# smd-to-breadboard2.net
KiCad netlist of a schematic drawn in EAGLE
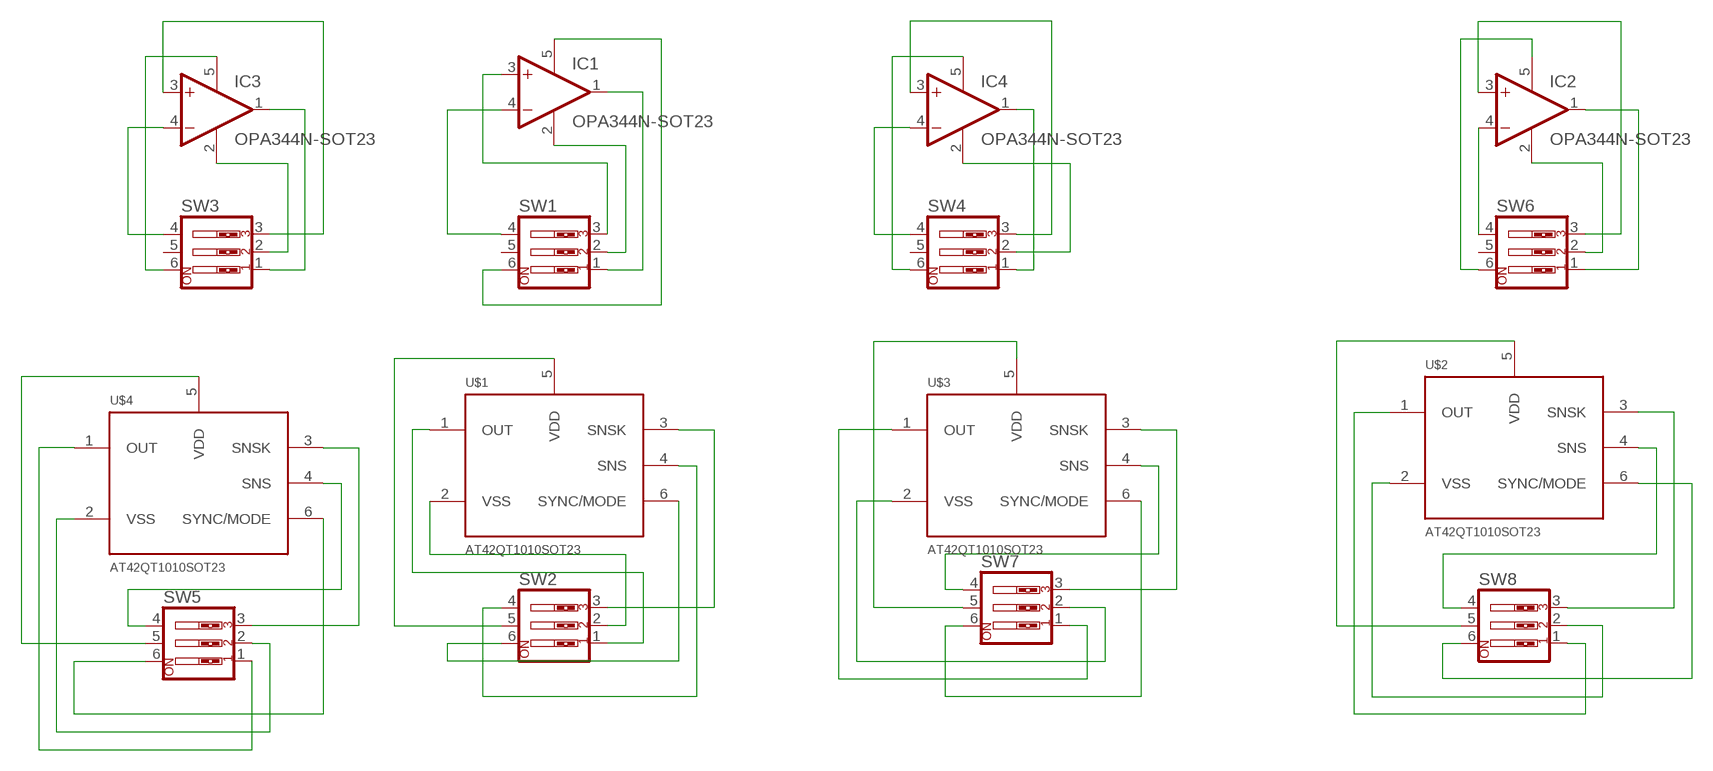
[diagram p0: schematic, sheet 1]

(export (version "E")
  (design (tool "Eeschema 10.0.6"))
  (components
    (comp (ref "IC1")
      (value "OPA344N-SOT23")
      (footprint "eagle-import:SOT23-5")
      (libsource (lib "eagle-import") (part "OPA-SOT23344N"))
    )
    (comp (ref "IC2")
      (value "OPA344N-SOT23")
      (footprint "eagle-import:SOT23-5")
      (libsource (lib "eagle-import") (part "OPA-SOT23344N"))
    )
    (comp (ref "IC3")
      (value "OPA344N-SOT23")
      (footprint "eagle-import:SOT23-5")
      (libsource (lib "eagle-import") (part "OPA-SOT23344N"))
    )
    (comp (ref "IC4")
      (value "OPA344N-SOT23")
      (footprint "eagle-import:SOT23-5")
      (libsource (lib "eagle-import") (part "OPA-SOT23344N"))
    )
    (comp (ref "SW1")
      (value "SW_DIP-3")
      (footprint "eagle-import:EDG-03")
      (libsource (lib "eagle-import") (part "SW_DIP-3"))
    )
    (comp (ref "SW2")
      (value "SW_DIP-3")
      (footprint "eagle-import:EDG-03")
      (libsource (lib "eagle-import") (part "SW_DIP-3"))
    )
    (comp (ref "SW3")
      (value "SW_DIP-3")
      (footprint "eagle-import:EDG-03")
      (libsource (lib "eagle-import") (part "SW_DIP-3"))
    )
    (comp (ref "SW4")
      (value "SW_DIP-3")
      (footprint "eagle-import:EDG-03")
      (libsource (lib "eagle-import") (part "SW_DIP-3"))
    )
    (comp (ref "SW5")
      (value "SW_DIP-3")
      (footprint "eagle-import:EDG-03")
      (libsource (lib "eagle-import") (part "SW_DIP-3"))
    )
    (comp (ref "SW6")
      (value "SW_DIP-3")
      (footprint "eagle-import:EDG-03")
      (libsource (lib "eagle-import") (part "SW_DIP-3"))
    )
    (comp (ref "SW7")
      (value "SW_DIP-3")
      (footprint "eagle-import:EDG-03")
      (libsource (lib "eagle-import") (part "SW_DIP-3"))
    )
    (comp (ref "SW8")
      (value "SW_DIP-3")
      (footprint "eagle-import:EDG-03")
      (libsource (lib "eagle-import") (part "SW_DIP-3"))
    )
    (comp (ref "U$1")
      (value "AT42QT1010SOT23")
      (footprint "eagle-import:SOT23-6")
      (libsource (lib "eagle-import") (part "AT42QT1010SOT23"))
    )
    (comp (ref "U$2")
      (value "AT42QT1010SOT23")
      (footprint "eagle-import:SOT23-6")
      (libsource (lib "eagle-import") (part "AT42QT1010SOT23"))
    )
    (comp (ref "U$3")
      (value "AT42QT1010SOT23")
      (footprint "eagle-import:SOT23-6")
      (libsource (lib "eagle-import") (part "AT42QT1010SOT23"))
    )
    (comp (ref "U$4")
      (value "AT42QT1010SOT23")
      (footprint "eagle-import:SOT23-6")
      (libsource (lib "eagle-import") (part "AT42QT1010SOT23"))
    )
  )
  (nets
    (net (code "1") (name "Net-(IC1-+IN)") (class "Default")
      (node (ref "IC1") (pin "3") (pinfunction "+IN_3") (pintype "input"))
      (node (ref "SW1") (pin "3") (pinfunction "3_3") (pintype "passive"))
    )
    (net (code "2") (name "Net-(IC1--IN)") (class "Default")
      (node (ref "IC1") (pin "4") (pinfunction "-IN_4") (pintype "input"))
      (node (ref "SW1") (pin "4") (pinfunction "4_4") (pintype "passive"))
    )
    (net (code "3") (name "Net-(IC1-OUT)") (class "Default")
      (node (ref "IC1") (pin "1") (pinfunction "OUT_1") (pintype "output"))
      (node (ref "SW1") (pin "1") (pinfunction "1_1") (pintype "passive"))
    )
    (net (code "4") (name "Net-(IC1-V+)") (class "Default")
      (node (ref "IC1") (pin "5") (pinfunction "V+_5") (pintype "power_in"))
      (node (ref "SW1") (pin "6") (pinfunction "6_6") (pintype "passive"))
    )
    (net (code "5") (name "Net-(IC1-V-)") (class "Default")
      (node (ref "IC1") (pin "2") (pinfunction "V-_2") (pintype "power_in"))
      (node (ref "SW1") (pin "2") (pinfunction "2_2") (pintype "passive"))
    )
    (net (code "6") (name "Net-(IC2-+IN)") (class "Default")
      (node (ref "IC2") (pin "3") (pinfunction "+IN_3") (pintype "input"))
      (node (ref "SW6") (pin "3") (pinfunction "3_3") (pintype "passive"))
    )
    (net (code "7") (name "Net-(IC2--IN)") (class "Default")
      (node (ref "IC2") (pin "4") (pinfunction "-IN_4") (pintype "input"))
      (node (ref "SW6") (pin "4") (pinfunction "4_4") (pintype "passive"))
    )
    (net (code "8") (name "Net-(IC2-OUT)") (class "Default")
      (node (ref "IC2") (pin "1") (pinfunction "OUT_1") (pintype "output"))
      (node (ref "SW6") (pin "1") (pinfunction "1_1") (pintype "passive"))
    )
    (net (code "9") (name "Net-(IC2-V+)") (class "Default")
      (node (ref "IC2") (pin "5") (pinfunction "V+_5") (pintype "power_in"))
      (node (ref "SW6") (pin "6") (pinfunction "6_6") (pintype "passive"))
    )
    (net (code "10") (name "Net-(IC2-V-)") (class "Default")
      (node (ref "IC2") (pin "2") (pinfunction "V-_2") (pintype "power_in"))
      (node (ref "SW6") (pin "2") (pinfunction "2_2") (pintype "passive"))
    )
    (net (code "11") (name "Net-(IC3-+IN)") (class "Default")
      (node (ref "IC3") (pin "3") (pinfunction "+IN_3") (pintype "input"))
      (node (ref "SW3") (pin "3") (pinfunction "3_3") (pintype "passive"))
    )
    (net (code "12") (name "Net-(IC3--IN)") (class "Default")
      (node (ref "IC3") (pin "4") (pinfunction "-IN_4") (pintype "input"))
      (node (ref "SW3") (pin "4") (pinfunction "4_4") (pintype "passive"))
    )
    (net (code "13") (name "Net-(IC3-OUT)") (class "Default")
      (node (ref "IC3") (pin "1") (pinfunction "OUT_1") (pintype "output"))
      (node (ref "SW3") (pin "1") (pinfunction "1_1") (pintype "passive"))
    )
    (net (code "14") (name "Net-(IC3-V+)") (class "Default")
      (node (ref "IC3") (pin "5") (pinfunction "V+_5") (pintype "power_in"))
      (node (ref "SW3") (pin "6") (pinfunction "6_6") (pintype "passive"))
    )
    (net (code "15") (name "Net-(IC3-V-)") (class "Default")
      (node (ref "IC3") (pin "2") (pinfunction "V-_2") (pintype "power_in"))
      (node (ref "SW3") (pin "2") (pinfunction "2_2") (pintype "passive"))
    )
    (net (code "16") (name "Net-(IC4-+IN)") (class "Default")
      (node (ref "IC4") (pin "3") (pinfunction "+IN_3") (pintype "input"))
      (node (ref "SW4") (pin "3") (pinfunction "3_3") (pintype "passive"))
    )
    (net (code "17") (name "Net-(IC4--IN)") (class "Default")
      (node (ref "IC4") (pin "4") (pinfunction "-IN_4") (pintype "input"))
      (node (ref "SW4") (pin "4") (pinfunction "4_4") (pintype "passive"))
    )
    (net (code "18") (name "Net-(IC4-OUT)") (class "Default")
      (node (ref "IC4") (pin "1") (pinfunction "OUT_1") (pintype "output"))
      (node (ref "SW4") (pin "1") (pinfunction "1_1") (pintype "passive"))
    )
    (net (code "19") (name "Net-(IC4-V+)") (class "Default")
      (node (ref "IC4") (pin "5") (pinfunction "V+_5") (pintype "power_in"))
      (node (ref "SW4") (pin "6") (pinfunction "6_6") (pintype "passive"))
    )
    (net (code "20") (name "Net-(IC4-V-)") (class "Default")
      (node (ref "IC4") (pin "2") (pinfunction "V-_2") (pintype "power_in"))
      (node (ref "SW4") (pin "2") (pinfunction "2_2") (pintype "passive"))
    )
    (net (code "21") (name "Net-(U$1-OUT)") (class "Default")
      (node (ref "SW2") (pin "1") (pinfunction "1_1") (pintype "passive"))
      (node (ref "U$1") (pin "1") (pinfunction "OUT_1") (pintype "bidirectional"))
    )
    (net (code "22") (name "Net-(U$1-SNS)") (class "Default")
      (node (ref "SW2") (pin "4") (pinfunction "4_4") (pintype "passive"))
      (node (ref "U$1") (pin "4") (pinfunction "SNS_4") (pintype "bidirectional"))
    )
    (net (code "23") (name "Net-(U$1-SNSK)") (class "Default")
      (node (ref "SW2") (pin "3") (pinfunction "3_3") (pintype "passive"))
      (node (ref "U$1") (pin "3") (pinfunction "SNSK_3") (pintype "bidirectional"))
    )
    (net (code "24") (name "Net-(U$1-SYNC{slash}MODE)") (class "Default")
      (node (ref "SW2") (pin "6") (pinfunction "6_6") (pintype "passive"))
      (node (ref "U$1") (pin "6") (pinfunction "SYNC/MODE_6") (pintype "bidirectional"))
    )
    (net (code "25") (name "Net-(U$1-VDD)") (class "Default")
      (node (ref "SW2") (pin "5") (pinfunction "5_5") (pintype "passive"))
      (node (ref "U$1") (pin "5") (pinfunction "VDD_5") (pintype "bidirectional"))
    )
    (net (code "26") (name "Net-(U$1-VSS)") (class "Default")
      (node (ref "SW2") (pin "2") (pinfunction "2_2") (pintype "passive"))
      (node (ref "U$1") (pin "2") (pinfunction "VSS_2") (pintype "bidirectional"))
    )
    (net (code "27") (name "Net-(U$2-OUT)") (class "Default")
      (node (ref "SW8") (pin "1") (pinfunction "1_1") (pintype "passive"))
      (node (ref "U$2") (pin "1") (pinfunction "OUT_1") (pintype "bidirectional"))
    )
    (net (code "28") (name "Net-(U$2-SNS)") (class "Default")
      (node (ref "SW8") (pin "4") (pinfunction "4_4") (pintype "passive"))
      (node (ref "U$2") (pin "4") (pinfunction "SNS_4") (pintype "bidirectional"))
    )
    (net (code "29") (name "Net-(U$2-SNSK)") (class "Default")
      (node (ref "SW8") (pin "3") (pinfunction "3_3") (pintype "passive"))
      (node (ref "U$2") (pin "3") (pinfunction "SNSK_3") (pintype "bidirectional"))
    )
    (net (code "30") (name "Net-(U$2-SYNC{slash}MODE)") (class "Default")
      (node (ref "SW8") (pin "6") (pinfunction "6_6") (pintype "passive"))
      (node (ref "U$2") (pin "6") (pinfunction "SYNC/MODE_6") (pintype "bidirectional"))
    )
    (net (code "31") (name "Net-(U$2-VDD)") (class "Default")
      (node (ref "SW8") (pin "5") (pinfunction "5_5") (pintype "passive"))
      (node (ref "U$2") (pin "5") (pinfunction "VDD_5") (pintype "bidirectional"))
    )
    (net (code "32") (name "Net-(U$2-VSS)") (class "Default")
      (node (ref "SW8") (pin "2") (pinfunction "2_2") (pintype "passive"))
      (node (ref "U$2") (pin "2") (pinfunction "VSS_2") (pintype "bidirectional"))
    )
    (net (code "33") (name "Net-(U$3-OUT)") (class "Default")
      (node (ref "SW7") (pin "1") (pinfunction "1_1") (pintype "passive"))
      (node (ref "U$3") (pin "1") (pinfunction "OUT_1") (pintype "bidirectional"))
    )
    (net (code "34") (name "Net-(U$3-SNS)") (class "Default")
      (node (ref "SW7") (pin "4") (pinfunction "4_4") (pintype "passive"))
      (node (ref "U$3") (pin "4") (pinfunction "SNS_4") (pintype "bidirectional"))
    )
    (net (code "35") (name "Net-(U$3-SNSK)") (class "Default")
      (node (ref "SW7") (pin "3") (pinfunction "3_3") (pintype "passive"))
      (node (ref "U$3") (pin "3") (pinfunction "SNSK_3") (pintype "bidirectional"))
    )
    (net (code "36") (name "Net-(U$3-SYNC{slash}MODE)") (class "Default")
      (node (ref "SW7") (pin "6") (pinfunction "6_6") (pintype "passive"))
      (node (ref "U$3") (pin "6") (pinfunction "SYNC/MODE_6") (pintype "bidirectional"))
    )
    (net (code "37") (name "Net-(U$3-VDD)") (class "Default")
      (node (ref "SW7") (pin "5") (pinfunction "5_5") (pintype "passive"))
      (node (ref "U$3") (pin "5") (pinfunction "VDD_5") (pintype "bidirectional"))
    )
    (net (code "38") (name "Net-(U$3-VSS)") (class "Default")
      (node (ref "SW7") (pin "2") (pinfunction "2_2") (pintype "passive"))
      (node (ref "U$3") (pin "2") (pinfunction "VSS_2") (pintype "bidirectional"))
    )
    (net (code "39") (name "Net-(U$4-OUT)") (class "Default")
      (node (ref "SW5") (pin "1") (pinfunction "1_1") (pintype "passive"))
      (node (ref "U$4") (pin "1") (pinfunction "OUT_1") (pintype "bidirectional"))
    )
    (net (code "40") (name "Net-(U$4-SNS)") (class "Default")
      (node (ref "SW5") (pin "4") (pinfunction "4_4") (pintype "passive"))
      (node (ref "U$4") (pin "4") (pinfunction "SNS_4") (pintype "bidirectional"))
    )
    (net (code "41") (name "Net-(U$4-SNSK)") (class "Default")
      (node (ref "SW5") (pin "3") (pinfunction "3_3") (pintype "passive"))
      (node (ref "U$4") (pin "3") (pinfunction "SNSK_3") (pintype "bidirectional"))
    )
    (net (code "42") (name "Net-(U$4-SYNC{slash}MODE)") (class "Default")
      (node (ref "SW5") (pin "6") (pinfunction "6_6") (pintype "passive"))
      (node (ref "U$4") (pin "6") (pinfunction "SYNC/MODE_6") (pintype "bidirectional"))
    )
    (net (code "43") (name "Net-(U$4-VDD)") (class "Default")
      (node (ref "SW5") (pin "5") (pinfunction "5_5") (pintype "passive"))
      (node (ref "U$4") (pin "5") (pinfunction "VDD_5") (pintype "bidirectional"))
    )
    (net (code "44") (name "Net-(U$4-VSS)") (class "Default")
      (node (ref "SW5") (pin "2") (pinfunction "2_2") (pintype "passive"))
      (node (ref "U$4") (pin "2") (pinfunction "VSS_2") (pintype "bidirectional"))
    )
    (net (code "45") (name "unconnected-(SW1-Pad5)") (class "Default")
      (node (ref "SW1") (pin "5") (pinfunction "5_5") (pintype "passive"))
    )
    (net (code "46") (name "unconnected-(SW3-Pad5)") (class "Default")
      (node (ref "SW3") (pin "5") (pinfunction "5_5") (pintype "passive"))
    )
    (net (code "47") (name "unconnected-(SW4-Pad5)") (class "Default")
      (node (ref "SW4") (pin "5") (pinfunction "5_5") (pintype "passive"))
    )
    (net (code "48") (name "unconnected-(SW6-Pad5)") (class "Default")
      (node (ref "SW6") (pin "5") (pinfunction "5_5") (pintype "passive"))
    )
  )
)
